# Pro_Trinket_Keyboard_V4_0.net
KiCad netlist of a schematic drawn in EAGLE
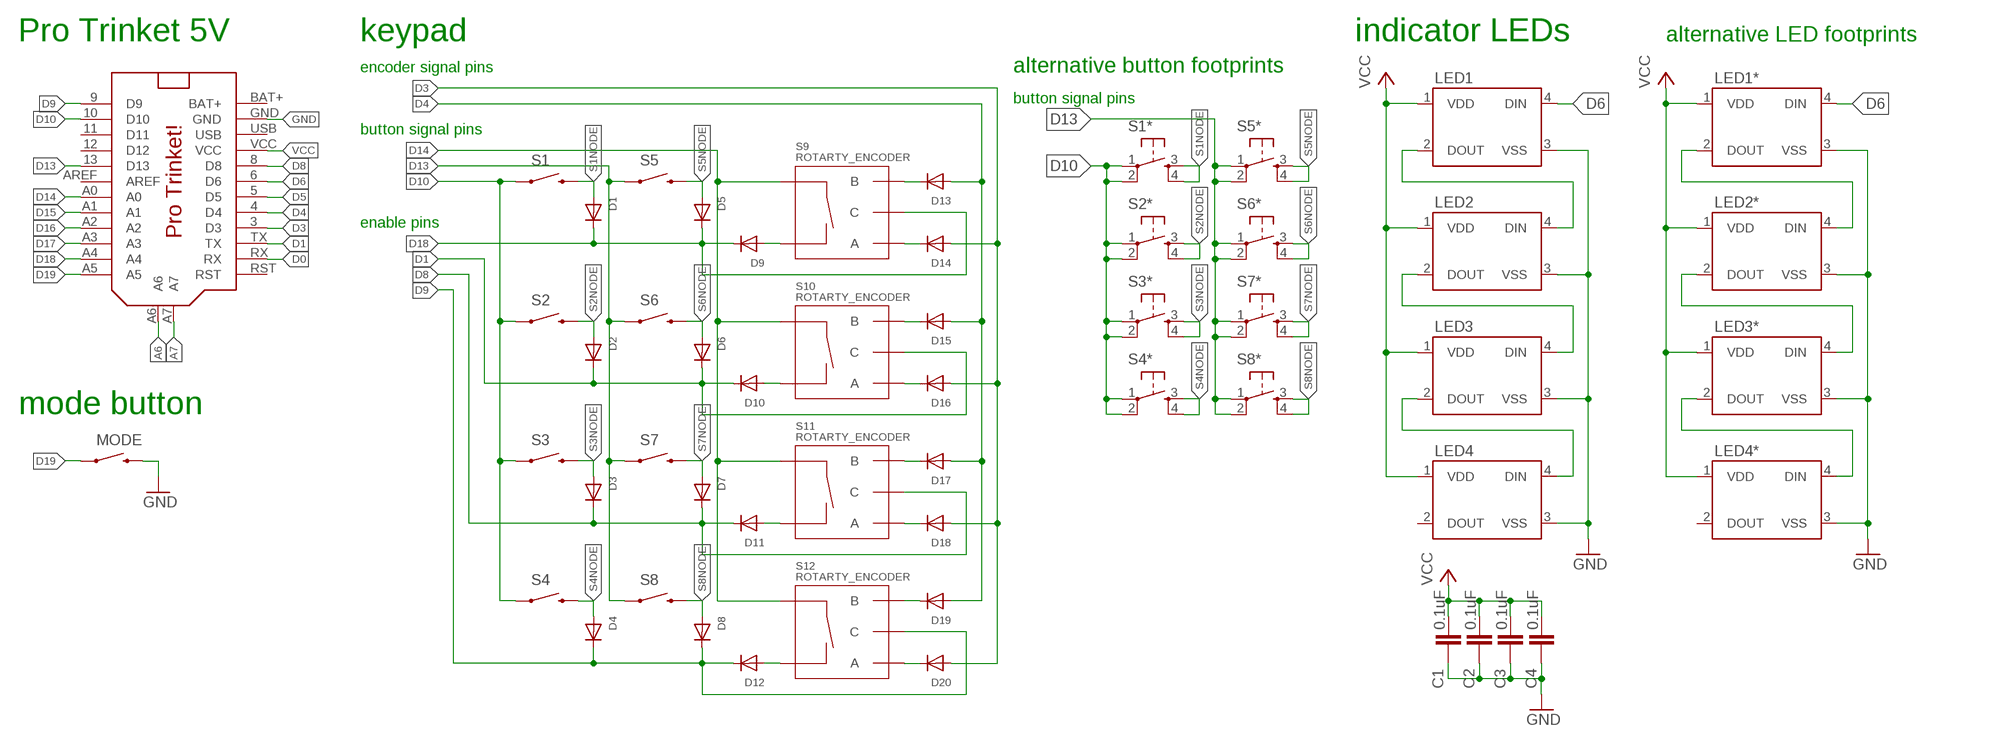
[diagram p0: schematic, sheet 1]

(export (version "E")
  (design (tool "Eeschema 10.0.6"))
  (components
    (comp (ref "C1")
      (value "0.1uF")
      (footprint "eagle-import:0603-CAP")
      (libsource (lib "eagle-import") (part "22PF-50V-5%(0603)"))
    )
    (comp (ref "C2")
      (value "0.1uF")
      (footprint "eagle-import:0603-CAP")
      (libsource (lib "eagle-import") (part "22PF-50V-5%(0603)"))
    )
    (comp (ref "C3")
      (value "0.1uF")
      (footprint "eagle-import:0603-CAP")
      (libsource (lib "eagle-import") (part "22PF-50V-5%(0603)"))
    )
    (comp (ref "C4")
      (value "0.1uF")
      (footprint "eagle-import:0603-CAP")
      (libsource (lib "eagle-import") (part "22PF-50V-5%(0603)"))
    )
    (comp (ref "D1")
      (value "DIODESOD-123")
      (footprint "eagle-import:SOD-123")
      (libsource (lib "eagle-import") (part "DIODESOD-123"))
    )
    (comp (ref "D2")
      (value "DIODESOD-123")
      (footprint "eagle-import:SOD-123")
      (libsource (lib "eagle-import") (part "DIODESOD-123"))
    )
    (comp (ref "D3")
      (value "DIODESOD-123")
      (footprint "eagle-import:SOD-123")
      (libsource (lib "eagle-import") (part "DIODESOD-123"))
    )
    (comp (ref "D4")
      (value "DIODESOD-123")
      (footprint "eagle-import:SOD-123")
      (libsource (lib "eagle-import") (part "DIODESOD-123"))
    )
    (comp (ref "D5")
      (value "DIODESOD-123")
      (footprint "eagle-import:SOD-123")
      (libsource (lib "eagle-import") (part "DIODESOD-123"))
    )
    (comp (ref "D6")
      (value "DIODESOD-123")
      (footprint "eagle-import:SOD-123")
      (libsource (lib "eagle-import") (part "DIODESOD-123"))
    )
    (comp (ref "D7")
      (value "DIODESOD-123")
      (footprint "eagle-import:SOD-123")
      (libsource (lib "eagle-import") (part "DIODESOD-123"))
    )
    (comp (ref "D8")
      (value "DIODESOD-123")
      (footprint "eagle-import:SOD-123")
      (libsource (lib "eagle-import") (part "DIODESOD-123"))
    )
    (comp (ref "D9")
      (value "DIODESOD-123")
      (footprint "eagle-import:SOD-123")
      (libsource (lib "eagle-import") (part "DIODESOD-123"))
    )
    (comp (ref "D10")
      (value "DIODESOD-123")
      (footprint "eagle-import:SOD-123")
      (libsource (lib "eagle-import") (part "DIODESOD-123"))
    )
    (comp (ref "D11")
      (value "DIODESOD-123")
      (footprint "eagle-import:SOD-123")
      (libsource (lib "eagle-import") (part "DIODESOD-123"))
    )
    (comp (ref "D12")
      (value "DIODESOD-123")
      (footprint "eagle-import:SOD-123")
      (libsource (lib "eagle-import") (part "DIODESOD-123"))
    )
    (comp (ref "D13")
      (value "DIODESOD-123")
      (footprint "eagle-import:SOD-123")
      (libsource (lib "eagle-import") (part "DIODESOD-123"))
    )
    (comp (ref "D14")
      (value "DIODESOD-123")
      (footprint "eagle-import:SOD-123")
      (libsource (lib "eagle-import") (part "DIODESOD-123"))
    )
    (comp (ref "D15")
      (value "DIODESOD-123")
      (footprint "eagle-import:SOD-123")
      (libsource (lib "eagle-import") (part "DIODESOD-123"))
    )
    (comp (ref "D16")
      (value "DIODESOD-123")
      (footprint "eagle-import:SOD-123")
      (libsource (lib "eagle-import") (part "DIODESOD-123"))
    )
    (comp (ref "D17")
      (value "DIODESOD-123")
      (footprint "eagle-import:SOD-123")
      (libsource (lib "eagle-import") (part "DIODESOD-123"))
    )
    (comp (ref "D18")
      (value "DIODESOD-123")
      (footprint "eagle-import:SOD-123")
      (libsource (lib "eagle-import") (part "DIODESOD-123"))
    )
    (comp (ref "D19")
      (value "DIODESOD-123")
      (footprint "eagle-import:SOD-123")
      (libsource (lib "eagle-import") (part "DIODESOD-123"))
    )
    (comp (ref "D20")
      (value "DIODESOD-123")
      (footprint "eagle-import:SOD-123")
      (libsource (lib "eagle-import") (part "DIODESOD-123"))
    )
    (comp (ref "LED1")
      (value "WS2812B")
      (footprint "eagle-import:WS2812B")
      (libsource (lib "eagle-import") (part "WS2812B"))
    )
    (comp (ref "LED1*")
      (value "WS2812B")
      (footprint "eagle-import:WS2812B")
      (libsource (lib "eagle-import") (part "WS2812B"))
    )
    (comp (ref "LED2")
      (value "WS2812B")
      (footprint "eagle-import:WS2812B")
      (libsource (lib "eagle-import") (part "WS2812B"))
    )
    (comp (ref "LED2*")
      (value "WS2812B")
      (footprint "eagle-import:WS2812B")
      (libsource (lib "eagle-import") (part "WS2812B"))
    )
    (comp (ref "LED3")
      (value "WS2812B")
      (footprint "eagle-import:WS2812B")
      (libsource (lib "eagle-import") (part "WS2812B"))
    )
    (comp (ref "LED3*")
      (value "WS2812B")
      (footprint "eagle-import:WS2812B")
      (libsource (lib "eagle-import") (part "WS2812B"))
    )
    (comp (ref "LED4")
      (value "WS2812B")
      (footprint "eagle-import:WS2812B")
      (libsource (lib "eagle-import") (part "WS2812B"))
    )
    (comp (ref "LED4*")
      (value "WS2812B")
      (footprint "eagle-import:WS2812B")
      (libsource (lib "eagle-import") (part "WS2812B"))
    )
    (comp (ref "MODE")
      (value "SWITCH-MOMENTARY-2SIDE_EZ")
      (footprint "eagle-import:TACTILE-PTH-SIDEEZ")
      (libsource (lib "eagle-import") (part "SWITCH-MOMENTARY-2SIDE_EZ"))
    )
    (comp (ref "PRO_TRINKET")
      (value "PRO_TRINKET")
      (footprint "eagle-import:PROTRINKET")
      (libsource (lib "eagle-import") (part "PRO_TRINKET"))
    )
    (comp (ref "S1")
      (value "SWITCH-MOMENTARY-212MM")
      (footprint "eagle-import:TACTILE-PTH-12MM")
      (libsource (lib "eagle-import") (part "SWITCH-MOMENTARY-212MM"))
    )
    (comp (ref "S1*")
      (value "TACTILE-SWITCH-PTH")
      (footprint "eagle-import:TAC-SWITCH-PTH")
      (libsource (lib "eagle-import") (part "TACTILE-SWITCH-PTH"))
    )
    (comp (ref "S2")
      (value "SWITCH-MOMENTARY-212MM")
      (footprint "eagle-import:TACTILE-PTH-12MM")
      (libsource (lib "eagle-import") (part "SWITCH-MOMENTARY-212MM"))
    )
    (comp (ref "S2*")
      (value "TACTILE-SWITCH-PTH")
      (footprint "eagle-import:TAC-SWITCH-PTH")
      (libsource (lib "eagle-import") (part "TACTILE-SWITCH-PTH"))
    )
    (comp (ref "S3")
      (value "SWITCH-MOMENTARY-212MM")
      (footprint "eagle-import:TACTILE-PTH-12MM")
      (libsource (lib "eagle-import") (part "SWITCH-MOMENTARY-212MM"))
    )
    (comp (ref "S3*")
      (value "TACTILE-SWITCH-PTH")
      (footprint "eagle-import:TAC-SWITCH-PTH")
      (libsource (lib "eagle-import") (part "TACTILE-SWITCH-PTH"))
    )
    (comp (ref "S4")
      (value "SWITCH-MOMENTARY-212MM")
      (footprint "eagle-import:TACTILE-PTH-12MM")
      (libsource (lib "eagle-import") (part "SWITCH-MOMENTARY-212MM"))
    )
    (comp (ref "S4*")
      (value "TACTILE-SWITCH-PTH")
      (footprint "eagle-import:TAC-SWITCH-PTH")
      (libsource (lib "eagle-import") (part "TACTILE-SWITCH-PTH"))
    )
    (comp (ref "S5")
      (value "SWITCH-MOMENTARY-212MM")
      (footprint "eagle-import:TACTILE-PTH-12MM")
      (libsource (lib "eagle-import") (part "SWITCH-MOMENTARY-212MM"))
    )
    (comp (ref "S5*")
      (value "TACTILE-SWITCH-PTH")
      (footprint "eagle-import:TAC-SWITCH-PTH")
      (libsource (lib "eagle-import") (part "TACTILE-SWITCH-PTH"))
    )
    (comp (ref "S6")
      (value "SWITCH-MOMENTARY-212MM")
      (footprint "eagle-import:TACTILE-PTH-12MM")
      (libsource (lib "eagle-import") (part "SWITCH-MOMENTARY-212MM"))
    )
    (comp (ref "S6*")
      (value "TACTILE-SWITCH-PTH")
      (footprint "eagle-import:TAC-SWITCH-PTH")
      (libsource (lib "eagle-import") (part "TACTILE-SWITCH-PTH"))
    )
    (comp (ref "S7")
      (value "SWITCH-MOMENTARY-212MM")
      (footprint "eagle-import:TACTILE-PTH-12MM")
      (libsource (lib "eagle-import") (part "SWITCH-MOMENTARY-212MM"))
    )
    (comp (ref "S7*")
      (value "TACTILE-SWITCH-PTH")
      (footprint "eagle-import:TAC-SWITCH-PTH")
      (libsource (lib "eagle-import") (part "TACTILE-SWITCH-PTH"))
    )
    (comp (ref "S8")
      (value "SWITCH-MOMENTARY-212MM")
      (footprint "eagle-import:TACTILE-PTH-12MM")
      (libsource (lib "eagle-import") (part "SWITCH-MOMENTARY-212MM"))
    )
    (comp (ref "S8*")
      (value "TACTILE-SWITCH-PTH")
      (footprint "eagle-import:TAC-SWITCH-PTH")
      (libsource (lib "eagle-import") (part "TACTILE-SWITCH-PTH"))
    )
    (comp (ref "S9")
      (value "ROTARTY_ENCODER")
      (footprint "eagle-import:ROTARY_ENC_PLAIN")
      (libsource (lib "eagle-import") (part "ROTARTY_ENCODER"))
    )
    (comp (ref "S10")
      (value "ROTARTY_ENCODER")
      (footprint "eagle-import:ROTARY_ENC_PLAIN")
      (libsource (lib "eagle-import") (part "ROTARTY_ENCODER"))
    )
    (comp (ref "S11")
      (value "ROTARTY_ENCODER")
      (footprint "eagle-import:ROTARY_ENC_PLAIN")
      (libsource (lib "eagle-import") (part "ROTARTY_ENCODER"))
    )
    (comp (ref "S12")
      (value "ROTARTY_ENCODER")
      (footprint "eagle-import:ROTARY_ENC_PLAIN")
      (libsource (lib "eagle-import") (part "ROTARTY_ENCODER"))
    )
  )
  (nets
    (net (code "1") (name "/BAT+") (class "Default")
      (node (ref "PRO_TRINKET") (pin "BAT+") (pinfunction "BAT+_BAT+") (pintype "power_in"))
    )
    (net (code "2") (name "/L1NODE") (class "Default")
      (node (ref "LED1") (pin "2") (pinfunction "DOUT_2") (pintype "output"))
      (node (ref "LED1*") (pin "2") (pinfunction "DOUT_2") (pintype "output"))
      (node (ref "LED2") (pin "4") (pinfunction "DIN_4") (pintype "input"))
      (node (ref "LED2*") (pin "4") (pinfunction "DIN_4") (pintype "input"))
    )
    (net (code "3") (name "/L2NODE") (class "Default")
      (node (ref "LED2") (pin "2") (pinfunction "DOUT_2") (pintype "output"))
      (node (ref "LED2*") (pin "2") (pinfunction "DOUT_2") (pintype "output"))
      (node (ref "LED3") (pin "4") (pinfunction "DIN_4") (pintype "input"))
      (node (ref "LED3*") (pin "4") (pinfunction "DIN_4") (pintype "input"))
    )
    (net (code "4") (name "/L3NODE") (class "Default")
      (node (ref "LED3") (pin "2") (pinfunction "DOUT_2") (pintype "output"))
      (node (ref "LED3*") (pin "2") (pinfunction "DOUT_2") (pintype "output"))
      (node (ref "LED4") (pin "4") (pinfunction "DIN_4") (pintype "input"))
      (node (ref "LED4*") (pin "4") (pinfunction "DIN_4") (pintype "input"))
    )
    (net (code "5") (name "/USB") (class "Default")
      (node (ref "PRO_TRINKET") (pin "USB") (pinfunction "USB_USB") (pintype "power_in"))
    )
    (net (code "6") (name "A6") (class "Default")
      (node (ref "PRO_TRINKET") (pin "A6") (pinfunction "A6_A6") (pintype "passive"))
    )
    (net (code "7") (name "A7") (class "Default")
      (node (ref "PRO_TRINKET") (pin "A7") (pinfunction "A7_A7") (pintype "passive"))
    )
    (net (code "8") (name "D0") (class "Default")
      (node (ref "PRO_TRINKET") (pin "RX") (pinfunction "RX_RX") (pintype "bidirectional"))
    )
    (net (code "9") (name "D1") (class "Default")
      (node (ref "D10") (pin "C") (pinfunction "C_C") (pintype "passive"))
      (node (ref "D2") (pin "C") (pinfunction "C_C") (pintype "passive"))
      (node (ref "D6") (pin "C") (pinfunction "C_C") (pintype "passive"))
      (node (ref "PRO_TRINKET") (pin "TX") (pinfunction "TX_TX") (pintype "bidirectional"))
      (node (ref "S10") (pin "C") (pinfunction "C_C") (pintype "bidirectional"))
    )
    (net (code "10") (name "D3") (class "Default")
      (node (ref "D14") (pin "A") (pinfunction "A_A") (pintype "passive"))
      (node (ref "D16") (pin "A") (pinfunction "A_A") (pintype "passive"))
      (node (ref "D18") (pin "A") (pinfunction "A_A") (pintype "passive"))
      (node (ref "D20") (pin "A") (pinfunction "A_A") (pintype "passive"))
      (node (ref "PRO_TRINKET") (pin "3") (pinfunction "D3_3") (pintype "bidirectional"))
    )
    (net (code "11") (name "D4") (class "Default")
      (node (ref "D13") (pin "A") (pinfunction "A_A") (pintype "passive"))
      (node (ref "D15") (pin "A") (pinfunction "A_A") (pintype "passive"))
      (node (ref "D17") (pin "A") (pinfunction "A_A") (pintype "passive"))
      (node (ref "D19") (pin "A") (pinfunction "A_A") (pintype "passive"))
      (node (ref "PRO_TRINKET") (pin "4") (pinfunction "D4_4") (pintype "bidirectional"))
    )
    (net (code "12") (name "D5") (class "Default")
      (node (ref "PRO_TRINKET") (pin "5") (pinfunction "D5_5") (pintype "bidirectional"))
    )
    (net (code "13") (name "D6") (class "Default")
      (node (ref "LED1") (pin "4") (pinfunction "DIN_4") (pintype "input"))
      (node (ref "LED1*") (pin "4") (pinfunction "DIN_4") (pintype "input"))
      (node (ref "PRO_TRINKET") (pin "6") (pinfunction "D6_6") (pintype "bidirectional"))
    )
    (net (code "14") (name "D8") (class "Default")
      (node (ref "D11") (pin "C") (pinfunction "C_C") (pintype "passive"))
      (node (ref "D3") (pin "C") (pinfunction "C_C") (pintype "passive"))
      (node (ref "D7") (pin "C") (pinfunction "C_C") (pintype "passive"))
      (node (ref "PRO_TRINKET") (pin "8") (pinfunction "D8_8") (pintype "bidirectional"))
      (node (ref "S11") (pin "C") (pinfunction "C_C") (pintype "bidirectional"))
    )
    (net (code "15") (name "D9") (class "Default")
      (node (ref "D12") (pin "C") (pinfunction "C_C") (pintype "passive"))
      (node (ref "D4") (pin "C") (pinfunction "C_C") (pintype "passive"))
      (node (ref "D8") (pin "C") (pinfunction "C_C") (pintype "passive"))
      (node (ref "PRO_TRINKET") (pin "9") (pinfunction "D9_9") (pintype "bidirectional"))
      (node (ref "S12") (pin "C") (pinfunction "C_C") (pintype "bidirectional"))
    )
    (net (code "16") (name "D10") (class "Default")
      (node (ref "PRO_TRINKET") (pin "10") (pinfunction "D10_10") (pintype "bidirectional"))
      (node (ref "S1") (pin "1") (pinfunction "1_1") (pintype "passive"))
      (node (ref "S1") (pin "2") (pinfunction "1_2") (pintype "passive"))
      (node (ref "S1*") (pin "1") (pinfunction "1_1") (pintype "passive"))
      (node (ref "S1*") (pin "2") (pinfunction "2_2") (pintype "passive"))
      (node (ref "S2") (pin "1") (pinfunction "1_1") (pintype "passive"))
      (node (ref "S2") (pin "2") (pinfunction "1_2") (pintype "passive"))
      (node (ref "S2*") (pin "1") (pinfunction "1_1") (pintype "passive"))
      (node (ref "S2*") (pin "2") (pinfunction "2_2") (pintype "passive"))
      (node (ref "S3") (pin "1") (pinfunction "1_1") (pintype "passive"))
      (node (ref "S3") (pin "2") (pinfunction "1_2") (pintype "passive"))
      (node (ref "S3*") (pin "1") (pinfunction "1_1") (pintype "passive"))
      (node (ref "S3*") (pin "2") (pinfunction "2_2") (pintype "passive"))
      (node (ref "S4") (pin "1") (pinfunction "1_1") (pintype "passive"))
      (node (ref "S4") (pin "2") (pinfunction "1_2") (pintype "passive"))
      (node (ref "S4*") (pin "1") (pinfunction "1_1") (pintype "passive"))
      (node (ref "S4*") (pin "2") (pinfunction "2_2") (pintype "passive"))
    )
    (net (code "17") (name "D13") (class "Default")
      (node (ref "PRO_TRINKET") (pin "13") (pinfunction "D13_13") (pintype "bidirectional"))
      (node (ref "S5") (pin "1") (pinfunction "1_1") (pintype "passive"))
      (node (ref "S5") (pin "2") (pinfunction "1_2") (pintype "passive"))
      (node (ref "S5*") (pin "1") (pinfunction "1_1") (pintype "passive"))
      (node (ref "S5*") (pin "2") (pinfunction "2_2") (pintype "passive"))
      (node (ref "S6") (pin "1") (pinfunction "1_1") (pintype "passive"))
      (node (ref "S6") (pin "2") (pinfunction "1_2") (pintype "passive"))
      (node (ref "S6*") (pin "1") (pinfunction "1_1") (pintype "passive"))
      (node (ref "S6*") (pin "2") (pinfunction "2_2") (pintype "passive"))
      (node (ref "S7") (pin "1") (pinfunction "1_1") (pintype "passive"))
      (node (ref "S7") (pin "2") (pinfunction "1_2") (pintype "passive"))
      (node (ref "S7*") (pin "1") (pinfunction "1_1") (pintype "passive"))
      (node (ref "S7*") (pin "2") (pinfunction "2_2") (pintype "passive"))
      (node (ref "S8") (pin "1") (pinfunction "1_1") (pintype "passive"))
      (node (ref "S8") (pin "2") (pinfunction "1_2") (pintype "passive"))
      (node (ref "S8*") (pin "1") (pinfunction "1_1") (pintype "passive"))
      (node (ref "S8*") (pin "2") (pinfunction "2_2") (pintype "passive"))
    )
    (net (code "18") (name "D14") (class "Default")
      (node (ref "PRO_TRINKET") (pin "A0") (pinfunction "A0_A0") (pintype "bidirectional"))
      (node (ref "S10") (pin "SW+") (pinfunction "SW+_SW+") (pintype "bidirectional"))
      (node (ref "S11") (pin "SW+") (pinfunction "SW+_SW+") (pintype "bidirectional"))
      (node (ref "S12") (pin "SW+") (pinfunction "SW+_SW+") (pintype "bidirectional"))
      (node (ref "S9") (pin "SW+") (pinfunction "SW+_SW+") (pintype "bidirectional"))
    )
    (net (code "19") (name "D15") (class "Default")
      (node (ref "PRO_TRINKET") (pin "A1") (pinfunction "A1_A1") (pintype "bidirectional"))
    )
    (net (code "20") (name "D16") (class "Default")
      (node (ref "PRO_TRINKET") (pin "A2") (pinfunction "A2_A2") (pintype "bidirectional"))
    )
    (net (code "21") (name "D17") (class "Default")
      (node (ref "PRO_TRINKET") (pin "A3") (pinfunction "A3_A3") (pintype "bidirectional"))
    )
    (net (code "22") (name "D18") (class "Default")
      (node (ref "D1") (pin "C") (pinfunction "C_C") (pintype "passive"))
      (node (ref "D5") (pin "C") (pinfunction "C_C") (pintype "passive"))
      (node (ref "D9") (pin "C") (pinfunction "C_C") (pintype "passive"))
      (node (ref "PRO_TRINKET") (pin "A4") (pinfunction "A4_A4") (pintype "bidirectional"))
      (node (ref "S9") (pin "C") (pinfunction "C_C") (pintype "bidirectional"))
    )
    (net (code "23") (name "D19") (class "Default")
      (node (ref "MODE") (pin "1") (pinfunction "1_1") (pintype "passive"))
      (node (ref "PRO_TRINKET") (pin "A5") (pinfunction "A5_A5") (pintype "bidirectional"))
    )
    (net (code "24") (name "GND") (class "Default")
      (node (ref "C1") (pin "1") (pinfunction "1_1") (pintype "passive"))
      (node (ref "C2") (pin "1") (pinfunction "1_1") (pintype "passive"))
      (node (ref "C3") (pin "1") (pinfunction "1_1") (pintype "passive"))
      (node (ref "C4") (pin "1") (pinfunction "1_1") (pintype "passive"))
      (node (ref "LED1") (pin "3") (pinfunction "VSS_3") (pintype "power_in"))
      (node (ref "LED1*") (pin "3") (pinfunction "VSS_3") (pintype "power_in"))
      (node (ref "LED2") (pin "3") (pinfunction "VSS_3") (pintype "power_in"))
      (node (ref "LED2*") (pin "3") (pinfunction "VSS_3") (pintype "power_in"))
      (node (ref "LED3") (pin "3") (pinfunction "VSS_3") (pintype "power_in"))
      (node (ref "LED3*") (pin "3") (pinfunction "VSS_3") (pintype "power_in"))
      (node (ref "LED4") (pin "3") (pinfunction "VSS_3") (pintype "power_in"))
      (node (ref "LED4*") (pin "3") (pinfunction "VSS_3") (pintype "power_in"))
      (node (ref "MODE") (pin "2") (pinfunction "2_2") (pintype "passive"))
      (node (ref "PRO_TRINKET") (pin "GND") (pinfunction "GND_GND") (pintype "power_in"))
    )
    (net (code "25") (name "Net-(D9-PadA)") (class "Default")
      (node (ref "D9") (pin "A") (pinfunction "A_A") (pintype "passive"))
      (node (ref "S9") (pin "SW-") (pinfunction "SW-_SW-") (pintype "bidirectional"))
    )
    (net (code "26") (name "Net-(D10-PadA)") (class "Default")
      (node (ref "D10") (pin "A") (pinfunction "A_A") (pintype "passive"))
      (node (ref "S10") (pin "SW-") (pinfunction "SW-_SW-") (pintype "bidirectional"))
    )
    (net (code "27") (name "Net-(D11-PadA)") (class "Default")
      (node (ref "D11") (pin "A") (pinfunction "A_A") (pintype "passive"))
      (node (ref "S11") (pin "SW-") (pinfunction "SW-_SW-") (pintype "bidirectional"))
    )
    (net (code "28") (name "Net-(D12-PadA)") (class "Default")
      (node (ref "D12") (pin "A") (pinfunction "A_A") (pintype "passive"))
      (node (ref "S12") (pin "SW-") (pinfunction "SW-_SW-") (pintype "bidirectional"))
    )
    (net (code "29") (name "Net-(D13-PadC)") (class "Default")
      (node (ref "D13") (pin "C") (pinfunction "C_C") (pintype "passive"))
      (node (ref "S9") (pin "B") (pinfunction "B_B") (pintype "bidirectional"))
    )
    (net (code "30") (name "Net-(D14-PadC)") (class "Default")
      (node (ref "D14") (pin "C") (pinfunction "C_C") (pintype "passive"))
      (node (ref "S9") (pin "A") (pinfunction "A_A") (pintype "bidirectional"))
    )
    (net (code "31") (name "Net-(D15-PadC)") (class "Default")
      (node (ref "D15") (pin "C") (pinfunction "C_C") (pintype "passive"))
      (node (ref "S10") (pin "B") (pinfunction "B_B") (pintype "bidirectional"))
    )
    (net (code "32") (name "Net-(D16-PadC)") (class "Default")
      (node (ref "D16") (pin "C") (pinfunction "C_C") (pintype "passive"))
      (node (ref "S10") (pin "A") (pinfunction "A_A") (pintype "bidirectional"))
    )
    (net (code "33") (name "Net-(D17-PadC)") (class "Default")
      (node (ref "D17") (pin "C") (pinfunction "C_C") (pintype "passive"))
      (node (ref "S11") (pin "B") (pinfunction "B_B") (pintype "bidirectional"))
    )
    (net (code "34") (name "Net-(D18-PadC)") (class "Default")
      (node (ref "D18") (pin "C") (pinfunction "C_C") (pintype "passive"))
      (node (ref "S11") (pin "A") (pinfunction "A_A") (pintype "bidirectional"))
    )
    (net (code "35") (name "Net-(D19-PadC)") (class "Default")
      (node (ref "D19") (pin "C") (pinfunction "C_C") (pintype "passive"))
      (node (ref "S12") (pin "B") (pinfunction "B_B") (pintype "bidirectional"))
    )
    (net (code "36") (name "Net-(D20-PadC)") (class "Default")
      (node (ref "D20") (pin "C") (pinfunction "C_C") (pintype "passive"))
      (node (ref "S12") (pin "A") (pinfunction "A_A") (pintype "bidirectional"))
    )
    (net (code "37") (name "S1NODE") (class "Default")
      (node (ref "D1") (pin "A") (pinfunction "A_A") (pintype "passive"))
      (node (ref "S1") (pin "3") (pinfunction "2_3") (pintype "passive"))
      (node (ref "S1") (pin "4") (pinfunction "2_4") (pintype "passive"))
      (node (ref "S1*") (pin "3") (pinfunction "3_3") (pintype "passive"))
      (node (ref "S1*") (pin "4") (pinfunction "4_4") (pintype "passive"))
    )
    (net (code "38") (name "S2NODE") (class "Default")
      (node (ref "D2") (pin "A") (pinfunction "A_A") (pintype "passive"))
      (node (ref "S2") (pin "3") (pinfunction "2_3") (pintype "passive"))
      (node (ref "S2") (pin "4") (pinfunction "2_4") (pintype "passive"))
      (node (ref "S2*") (pin "3") (pinfunction "3_3") (pintype "passive"))
      (node (ref "S2*") (pin "4") (pinfunction "4_4") (pintype "passive"))
    )
    (net (code "39") (name "S3NODE") (class "Default")
      (node (ref "D3") (pin "A") (pinfunction "A_A") (pintype "passive"))
      (node (ref "S3") (pin "3") (pinfunction "2_3") (pintype "passive"))
      (node (ref "S3") (pin "4") (pinfunction "2_4") (pintype "passive"))
      (node (ref "S3*") (pin "3") (pinfunction "3_3") (pintype "passive"))
      (node (ref "S3*") (pin "4") (pinfunction "4_4") (pintype "passive"))
    )
    (net (code "40") (name "S4NODE") (class "Default")
      (node (ref "D4") (pin "A") (pinfunction "A_A") (pintype "passive"))
      (node (ref "S4") (pin "3") (pinfunction "2_3") (pintype "passive"))
      (node (ref "S4") (pin "4") (pinfunction "2_4") (pintype "passive"))
      (node (ref "S4*") (pin "3") (pinfunction "3_3") (pintype "passive"))
      (node (ref "S4*") (pin "4") (pinfunction "4_4") (pintype "passive"))
    )
    (net (code "41") (name "S5NODE") (class "Default")
      (node (ref "D5") (pin "A") (pinfunction "A_A") (pintype "passive"))
      (node (ref "S5") (pin "3") (pinfunction "2_3") (pintype "passive"))
      (node (ref "S5") (pin "4") (pinfunction "2_4") (pintype "passive"))
      (node (ref "S5*") (pin "3") (pinfunction "3_3") (pintype "passive"))
      (node (ref "S5*") (pin "4") (pinfunction "4_4") (pintype "passive"))
    )
    (net (code "42") (name "S6NODE") (class "Default")
      (node (ref "D6") (pin "A") (pinfunction "A_A") (pintype "passive"))
      (node (ref "S6") (pin "3") (pinfunction "2_3") (pintype "passive"))
      (node (ref "S6") (pin "4") (pinfunction "2_4") (pintype "passive"))
      (node (ref "S6*") (pin "3") (pinfunction "3_3") (pintype "passive"))
      (node (ref "S6*") (pin "4") (pinfunction "4_4") (pintype "passive"))
    )
    (net (code "43") (name "S7NODE") (class "Default")
      (node (ref "D7") (pin "A") (pinfunction "A_A") (pintype "passive"))
      (node (ref "S7") (pin "3") (pinfunction "2_3") (pintype "passive"))
      (node (ref "S7") (pin "4") (pinfunction "2_4") (pintype "passive"))
      (node (ref "S7*") (pin "3") (pinfunction "3_3") (pintype "passive"))
      (node (ref "S7*") (pin "4") (pinfunction "4_4") (pintype "passive"))
    )
    (net (code "44") (name "S8NODE") (class "Default")
      (node (ref "D8") (pin "A") (pinfunction "A_A") (pintype "passive"))
      (node (ref "S8") (pin "3") (pinfunction "2_3") (pintype "passive"))
      (node (ref "S8") (pin "4") (pinfunction "2_4") (pintype "passive"))
      (node (ref "S8*") (pin "3") (pinfunction "3_3") (pintype "passive"))
      (node (ref "S8*") (pin "4") (pinfunction "4_4") (pintype "passive"))
    )
    (net (code "45") (name "VCC") (class "Default")
      (node (ref "C1") (pin "2") (pinfunction "2_2") (pintype "passive"))
      (node (ref "C2") (pin "2") (pinfunction "2_2") (pintype "passive"))
      (node (ref "C3") (pin "2") (pinfunction "2_2") (pintype "passive"))
      (node (ref "C4") (pin "2") (pinfunction "2_2") (pintype "passive"))
      (node (ref "LED1") (pin "1") (pinfunction "VDD_1") (pintype "power_in"))
      (node (ref "LED1*") (pin "1") (pinfunction "VDD_1") (pintype "power_in"))
      (node (ref "LED2") (pin "1") (pinfunction "VDD_1") (pintype "power_in"))
      (node (ref "LED2*") (pin "1") (pinfunction "VDD_1") (pintype "power_in"))
      (node (ref "LED3") (pin "1") (pinfunction "VDD_1") (pintype "power_in"))
      (node (ref "LED3*") (pin "1") (pinfunction "VDD_1") (pintype "power_in"))
      (node (ref "LED4") (pin "1") (pinfunction "VDD_1") (pintype "power_in"))
      (node (ref "LED4*") (pin "1") (pinfunction "VDD_1") (pintype "power_in"))
      (node (ref "PRO_TRINKET") (pin "VCC") (pinfunction "VCC_VCC") (pintype "power_in"))
    )
    (net (code "46") (name "unconnected-(LED4*-DOUT-Pad2)") (class "Default")
      (node (ref "LED4*") (pin "2") (pinfunction "DOUT_2") (pintype "output"))
    )
    (net (code "47") (name "unconnected-(LED4-DOUT-Pad2)") (class "Default")
      (node (ref "LED4") (pin "2") (pinfunction "DOUT_2") (pintype "output"))
    )
    (net (code "48") (name "unconnected-(PRO_TRINKET-D11-Pad11)") (class "Default")
      (node (ref "PRO_TRINKET") (pin "11") (pinfunction "D11_11") (pintype "bidirectional"))
    )
    (net (code "49") (name "unconnected-(PRO_TRINKET-D12-Pad12)") (class "Default")
      (node (ref "PRO_TRINKET") (pin "12") (pinfunction "D12_12") (pintype "bidirectional"))
    )
    (net (code "50") (name "unconnected-(PRO_TRINKET-PadAREF)") (class "Default")
      (node (ref "PRO_TRINKET") (pin "AREF") (pinfunction "AREF_AREF") (pintype "passive"))
    )
    (net (code "51") (name "unconnected-(PRO_TRINKET-PadRST)") (class "Default")
      (node (ref "PRO_TRINKET") (pin "RST") (pinfunction "RST_RST") (pintype "passive"))
    )
  )
)
